# mainboard.net
KiCad netlist of a schematic drawn in EAGLE
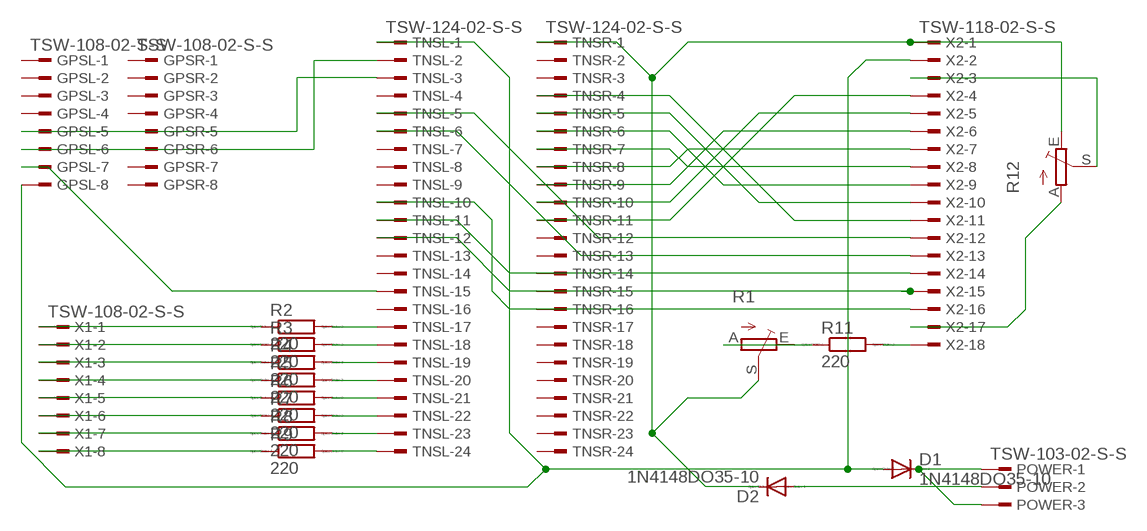
[diagram p0: schematic, sheet 1]

(export (version "E")
  (design (tool "Eeschema 10.0.6"))
  (components
    (comp (ref "D1")
      (value "1N4148DO35-10")
      (footprint "eagle-import:DO35-10")
      (libsource (lib "eagle-import") (part "1N4148DO35-10"))
    )
    (comp (ref "D2")
      (value "1N4148DO35-10")
      (footprint "eagle-import:DO35-10")
      (libsource (lib "eagle-import") (part "1N4148DO35-10"))
    )
    (comp (ref "GPSL")
      (value "TSW-108-02-S-S")
      (footprint "eagle-import:TSW-108-02-S-S")
      (libsource (lib "eagle-import") (part "TSW-108-02-S-S"))
    )
    (comp (ref "GPSR")
      (value "TSW-108-02-S-S")
      (footprint "eagle-import:TSW-108-02-S-S")
      (libsource (lib "eagle-import") (part "TSW-108-02-S-S"))
    )
    (comp (ref "POWER")
      (value "TSW-103-02-S-S")
      (footprint "eagle-import:TSW-103-02-S-S")
      (libsource (lib "eagle-import") (part "TSW-103-02-S-S"))
    )
    (comp (ref "R1")
      (value "TRIM_EU-CA6V")
      (footprint "eagle-import:CA6V")
      (libsource (lib "eagle-import") (part "TRIM_EU-CA6V"))
    )
    (comp (ref "R2")
      (value "220")
      (footprint "eagle-import:0207_10")
      (libsource (lib "eagle-import") (part "R0207/10"))
    )
    (comp (ref "R3")
      (value "220")
      (footprint "eagle-import:0207_10")
      (libsource (lib "eagle-import") (part "R0207/10"))
    )
    (comp (ref "R4")
      (value "220")
      (footprint "eagle-import:0207_10")
      (libsource (lib "eagle-import") (part "R0207/10"))
    )
    (comp (ref "R5")
      (value "220")
      (footprint "eagle-import:0207_10")
      (libsource (lib "eagle-import") (part "R0207/10"))
    )
    (comp (ref "R6")
      (value "220")
      (footprint "eagle-import:0207_10")
      (libsource (lib "eagle-import") (part "R0207/10"))
    )
    (comp (ref "R7")
      (value "220")
      (footprint "eagle-import:0207_10")
      (libsource (lib "eagle-import") (part "R0207/10"))
    )
    (comp (ref "R8")
      (value "220")
      (footprint "eagle-import:0207_10")
      (libsource (lib "eagle-import") (part "R0207/10"))
    )
    (comp (ref "R9")
      (value "220")
      (footprint "eagle-import:0207_10")
      (libsource (lib "eagle-import") (part "R0207/10"))
    )
    (comp (ref "R11")
      (value "220")
      (footprint "eagle-import:0207_10")
      (libsource (lib "eagle-import") (part "R0207/10"))
    )
    (comp (ref "R12")
      (value "TRIM_EU-CA6V")
      (footprint "eagle-import:CA6V")
      (libsource (lib "eagle-import") (part "TRIM_EU-CA6V"))
    )
    (comp (ref "TNSL")
      (value "TSW-124-02-S-S")
      (footprint "eagle-import:TSW-124-02-S-S")
      (libsource (lib "eagle-import") (part "TSW-124-02-S-S"))
    )
    (comp (ref "TNSR")
      (value "TSW-124-02-S-S")
      (footprint "eagle-import:TSW-124-02-S-S")
      (libsource (lib "eagle-import") (part "TSW-124-02-S-S"))
    )
    (comp (ref "X1")
      (value "TSW-108-02-S-S")
      (footprint "eagle-import:TSW-108-02-S-S")
      (libsource (lib "eagle-import") (part "TSW-108-02-S-S"))
    )
    (comp (ref "X2")
      (value "TSW-118-02-S-S")
      (footprint "eagle-import:TSW-118-02-S-S")
      (libsource (lib "eagle-import") (part "TSW-118-02-S-S"))
    )
  )
  (nets
    (net (code "1") (name "Net-(D2-PadC)") (class "Default")
      (node (ref "D2") (pin "C") (pinfunction "C_C") (pintype "passive"))
      (node (ref "R1") (pin "S") (pinfunction "S_S") (pintype "passive"))
      (node (ref "R12") (pin "E") (pinfunction "E_E") (pintype "passive"))
      (node (ref "TNSR") (pin "1") (pinfunction "1_1") (pintype "passive"))
      (node (ref "X2") (pin "1") (pinfunction "1_1") (pintype "passive"))
    )
    (net (code "2") (name "Net-(GPSLE-1)") (class "Default")
      (node (ref "GPSL") (pin "5") (pinfunction "1_5") (pintype "passive"))
      (node (ref "TNSL") (pin "3") (pinfunction "1_3") (pintype "passive"))
    )
    (net (code "3") (name "Net-(GPSLF-1)") (class "Default")
      (node (ref "GPSL") (pin "6") (pinfunction "1_6") (pintype "passive"))
      (node (ref "TNSL") (pin "2") (pinfunction "1_2") (pintype "passive"))
    )
    (net (code "4") (name "Net-(GPSLG-1)") (class "Default")
      (node (ref "GPSL") (pin "7") (pinfunction "1_7") (pintype "passive"))
      (node (ref "TNSL") (pin "15") (pinfunction "1_15") (pintype "passive"))
    )
    (net (code "5") (name "Net-(GPSLH-1)") (class "Default")
      (node (ref "D1") (pin "A") (pinfunction "A_A") (pintype "passive"))
      (node (ref "GPSL") (pin "8") (pinfunction "1_8") (pintype "passive"))
      (node (ref "TNSL") (pin "1") (pinfunction "1_1") (pintype "passive"))
      (node (ref "X2") (pin "2") (pinfunction "1_2") (pintype "passive"))
    )
    (net (code "6") (name "Net-(POWERB-1)") (class "Default")
      (node (ref "D2") (pin "A") (pinfunction "A_A") (pintype "passive"))
      (node (ref "POWER") (pin "2") (pinfunction "1_2") (pintype "passive"))
    )
    (net (code "7") (name "Net-(POWERC-1)") (class "Default")
      (node (ref "D1") (pin "C") (pinfunction "C_C") (pintype "passive"))
      (node (ref "POWER") (pin "1") (pinfunction "1_1") (pintype "passive"))
      (node (ref "POWER") (pin "3") (pinfunction "1_3") (pintype "passive"))
    )
    (net (code "8") (name "Net-(R1-PadA)") (class "Default")
      (node (ref "R1") (pin "A") (pinfunction "A_A") (pintype "passive"))
      (node (ref "R11") (pin "1") (pinfunction "1_1") (pintype "passive"))
    )
    (net (code "9") (name "Net-(R2-Pad1)") (class "Default")
      (node (ref "R2") (pin "1") (pinfunction "1_1") (pintype "passive"))
      (node (ref "X1") (pin "1") (pinfunction "1_1") (pintype "passive"))
    )
    (net (code "10") (name "Net-(TNSLB-1)") (class "Default")
      (node (ref "TNSL") (pin "10") (pinfunction "1_10") (pintype "passive"))
      (node (ref "X2") (pin "16") (pinfunction "1_16") (pintype "passive"))
    )
    (net (code "11") (name "Net-(TNSLC-1)") (class "Default")
      (node (ref "TNSL") (pin "11") (pinfunction "1_11") (pintype "passive"))
      (node (ref "X2") (pin "14") (pinfunction "1_14") (pintype "passive"))
    )
    (net (code "12") (name "Net-(TNSLD-1)") (class "Default")
      (node (ref "TNSL") (pin "12") (pinfunction "1_12") (pintype "passive"))
      (node (ref "X2") (pin "15") (pinfunction "1_15") (pintype "passive"))
    )
    (net (code "13") (name "Net-(TNSLI-1)") (class "Default")
      (node (ref "R2") (pin "2") (pinfunction "2_2") (pintype "passive"))
      (node (ref "TNSL") (pin "17") (pinfunction "1_17") (pintype "passive"))
    )
    (net (code "14") (name "Net-(TNSLJ-1)") (class "Default")
      (node (ref "R3") (pin "2") (pinfunction "2_2") (pintype "passive"))
      (node (ref "TNSL") (pin "18") (pinfunction "1_18") (pintype "passive"))
    )
    (net (code "15") (name "Net-(TNSLK-1)") (class "Default")
      (node (ref "R4") (pin "2") (pinfunction "2_2") (pintype "passive"))
      (node (ref "TNSL") (pin "19") (pinfunction "1_19") (pintype "passive"))
    )
    (net (code "16") (name "Net-(TNSLM-1)") (class "Default")
      (node (ref "R5") (pin "2") (pinfunction "2_2") (pintype "passive"))
      (node (ref "TNSL") (pin "20") (pinfunction "1_20") (pintype "passive"))
    )
    (net (code "17") (name "Net-(TNSLN-1)") (class "Default")
      (node (ref "R6") (pin "2") (pinfunction "2_2") (pintype "passive"))
      (node (ref "TNSL") (pin "21") (pinfunction "1_21") (pintype "passive"))
    )
    (net (code "18") (name "Net-(TNSLO-1)") (class "Default")
      (node (ref "R7") (pin "2") (pinfunction "2_2") (pintype "passive"))
      (node (ref "TNSL") (pin "22") (pinfunction "1_22") (pintype "passive"))
    )
    (net (code "19") (name "Net-(TNSLP-1)") (class "Default")
      (node (ref "R8") (pin "2") (pinfunction "2_2") (pintype "passive"))
      (node (ref "TNSL") (pin "23") (pinfunction "1_23") (pintype "passive"))
    )
    (net (code "20") (name "Net-(TNSLQ-1)") (class "Default")
      (node (ref "R9") (pin "2") (pinfunction "2_2") (pintype "passive"))
      (node (ref "TNSL") (pin "24") (pinfunction "1_24") (pintype "passive"))
    )
    (net (code "21") (name "Net-(TNSLT-1)") (class "Default")
      (node (ref "TNSL") (pin "5") (pinfunction "1_5") (pintype "passive"))
      (node (ref "X2") (pin "12") (pinfunction "1_12") (pintype "passive"))
    )
    (net (code "22") (name "Net-(TNSLU-1)") (class "Default")
      (node (ref "TNSL") (pin "6") (pinfunction "1_6") (pintype "passive"))
      (node (ref "X2") (pin "13") (pinfunction "1_13") (pintype "passive"))
    )
    (net (code "23") (name "Net-(TNSRB-1)") (class "Default")
      (node (ref "TNSR") (pin "10") (pinfunction "1_10") (pintype "passive"))
      (node (ref "X2") (pin "5") (pinfunction "1_5") (pintype "passive"))
    )
    (net (code "24") (name "Net-(TNSRC-1)") (class "Default")
      (node (ref "TNSR") (pin "11") (pinfunction "1_11") (pintype "passive"))
      (node (ref "X2") (pin "4") (pinfunction "1_4") (pintype "passive"))
    )
    (net (code "25") (name "Net-(TNSRS-1)") (class "Default")
      (node (ref "TNSR") (pin "4") (pinfunction "1_4") (pintype "passive"))
      (node (ref "X2") (pin "11") (pinfunction "1_11") (pintype "passive"))
    )
    (net (code "26") (name "Net-(TNSRT-1)") (class "Default")
      (node (ref "TNSR") (pin "5") (pinfunction "1_5") (pintype "passive"))
      (node (ref "X2") (pin "10") (pinfunction "1_10") (pintype "passive"))
    )
    (net (code "27") (name "Net-(TNSRU-1)") (class "Default")
      (node (ref "TNSR") (pin "6") (pinfunction "1_6") (pintype "passive"))
      (node (ref "X2") (pin "9") (pinfunction "1_9") (pintype "passive"))
    )
    (net (code "28") (name "Net-(TNSRV-1)") (class "Default")
      (node (ref "TNSR") (pin "7") (pinfunction "1_7") (pintype "passive"))
      (node (ref "X2") (pin "8") (pinfunction "1_8") (pintype "passive"))
    )
    (net (code "29") (name "Net-(TNSRW-1)") (class "Default")
      (node (ref "TNSR") (pin "8") (pinfunction "1_8") (pintype "passive"))
      (node (ref "X2") (pin "7") (pinfunction "1_7") (pintype "passive"))
    )
    (net (code "30") (name "Net-(TNSRX-1)") (class "Default")
      (node (ref "TNSR") (pin "9") (pinfunction "1_9") (pintype "passive"))
      (node (ref "X2") (pin "6") (pinfunction "1_6") (pintype "passive"))
    )
    (net (code "31") (name "Net-(X1B-1)") (class "Default")
      (node (ref "R3") (pin "1") (pinfunction "1_1") (pintype "passive"))
      (node (ref "X1") (pin "2") (pinfunction "1_2") (pintype "passive"))
    )
    (net (code "32") (name "Net-(X1C-1)") (class "Default")
      (node (ref "R4") (pin "1") (pinfunction "1_1") (pintype "passive"))
      (node (ref "X1") (pin "3") (pinfunction "1_3") (pintype "passive"))
    )
    (net (code "33") (name "Net-(X1D-1)") (class "Default")
      (node (ref "R5") (pin "1") (pinfunction "1_1") (pintype "passive"))
      (node (ref "X1") (pin "4") (pinfunction "1_4") (pintype "passive"))
    )
    (net (code "34") (name "Net-(X1E-1)") (class "Default")
      (node (ref "R6") (pin "1") (pinfunction "1_1") (pintype "passive"))
      (node (ref "X1") (pin "5") (pinfunction "1_5") (pintype "passive"))
    )
    (net (code "35") (name "Net-(X1F-1)") (class "Default")
      (node (ref "R7") (pin "1") (pinfunction "1_1") (pintype "passive"))
      (node (ref "X1") (pin "6") (pinfunction "1_6") (pintype "passive"))
    )
    (net (code "36") (name "Net-(X1G-1)") (class "Default")
      (node (ref "R8") (pin "1") (pinfunction "1_1") (pintype "passive"))
      (node (ref "X1") (pin "7") (pinfunction "1_7") (pintype "passive"))
    )
    (net (code "37") (name "Net-(X1H-1)") (class "Default")
      (node (ref "R9") (pin "1") (pinfunction "1_1") (pintype "passive"))
      (node (ref "X1") (pin "8") (pinfunction "1_8") (pintype "passive"))
    )
    (net (code "38") (name "Net-(X2I-1)") (class "Default")
      (node (ref "R12") (pin "A") (pinfunction "A_A") (pintype "passive"))
      (node (ref "X2") (pin "17") (pinfunction "1_17") (pintype "passive"))
    )
    (net (code "39") (name "Net-(X2J-1)") (class "Default")
      (node (ref "R11") (pin "2") (pinfunction "2_2") (pintype "passive"))
      (node (ref "X2") (pin "18") (pinfunction "1_18") (pintype "passive"))
    )
    (net (code "40") (name "Net-(X2L-1)") (class "Default")
      (node (ref "R12") (pin "S") (pinfunction "S_S") (pintype "passive"))
      (node (ref "X2") (pin "3") (pinfunction "1_3") (pintype "passive"))
    )
    (net (code "41") (name "unconnected-(GPSL-Pad1)") (class "Default")
      (node (ref "GPSL") (pin "1") (pinfunction "1_1") (pintype "passive"))
    )
    (net (code "42") (name "unconnected-(GPSLB-1-Pad2)") (class "Default")
      (node (ref "GPSL") (pin "2") (pinfunction "1_2") (pintype "passive"))
    )
    (net (code "43") (name "unconnected-(GPSLC-1-Pad3)") (class "Default")
      (node (ref "GPSL") (pin "3") (pinfunction "1_3") (pintype "passive"))
    )
    (net (code "44") (name "unconnected-(GPSLD-1-Pad4)") (class "Default")
      (node (ref "GPSL") (pin "4") (pinfunction "1_4") (pintype "passive"))
    )
    (net (code "45") (name "unconnected-(GPSR-Pad1)") (class "Default")
      (node (ref "GPSR") (pin "1") (pinfunction "1_1") (pintype "passive"))
    )
    (net (code "46") (name "unconnected-(GPSRB-1-Pad2)") (class "Default")
      (node (ref "GPSR") (pin "2") (pinfunction "1_2") (pintype "passive"))
    )
    (net (code "47") (name "unconnected-(GPSRC-1-Pad3)") (class "Default")
      (node (ref "GPSR") (pin "3") (pinfunction "1_3") (pintype "passive"))
    )
    (net (code "48") (name "unconnected-(GPSRD-1-Pad4)") (class "Default")
      (node (ref "GPSR") (pin "4") (pinfunction "1_4") (pintype "passive"))
    )
    (net (code "49") (name "unconnected-(GPSRE-1-Pad5)") (class "Default")
      (node (ref "GPSR") (pin "5") (pinfunction "1_5") (pintype "passive"))
    )
    (net (code "50") (name "unconnected-(GPSRF-1-Pad6)") (class "Default")
      (node (ref "GPSR") (pin "6") (pinfunction "1_6") (pintype "passive"))
    )
    (net (code "51") (name "unconnected-(GPSRG-1-Pad7)") (class "Default")
      (node (ref "GPSR") (pin "7") (pinfunction "1_7") (pintype "passive"))
    )
    (net (code "52") (name "unconnected-(GPSRH-1-Pad8)") (class "Default")
      (node (ref "GPSR") (pin "8") (pinfunction "1_8") (pintype "passive"))
    )
    (net (code "53") (name "unconnected-(R1-PadE)") (class "Default")
      (node (ref "R1") (pin "E") (pinfunction "E_E") (pintype "passive"))
    )
    (net (code "54") (name "unconnected-(TNSLE-1-Pad13)") (class "Default")
      (node (ref "TNSL") (pin "13") (pinfunction "1_13") (pintype "passive"))
    )
    (net (code "55") (name "unconnected-(TNSLF-1-Pad14)") (class "Default")
      (node (ref "TNSL") (pin "14") (pinfunction "1_14") (pintype "passive"))
    )
    (net (code "56") (name "unconnected-(TNSLH-1-Pad16)") (class "Default")
      (node (ref "TNSL") (pin "16") (pinfunction "1_16") (pintype "passive"))
    )
    (net (code "57") (name "unconnected-(TNSLS-1-Pad4)") (class "Default")
      (node (ref "TNSL") (pin "4") (pinfunction "1_4") (pintype "passive"))
    )
    (net (code "58") (name "unconnected-(TNSLV-1-Pad7)") (class "Default")
      (node (ref "TNSL") (pin "7") (pinfunction "1_7") (pintype "passive"))
    )
    (net (code "59") (name "unconnected-(TNSLW-1-Pad8)") (class "Default")
      (node (ref "TNSL") (pin "8") (pinfunction "1_8") (pintype "passive"))
    )
    (net (code "60") (name "unconnected-(TNSLX-1-Pad9)") (class "Default")
      (node (ref "TNSL") (pin "9") (pinfunction "1_9") (pintype "passive"))
    )
    (net (code "61") (name "unconnected-(TNSRD-1-Pad12)") (class "Default")
      (node (ref "TNSR") (pin "12") (pinfunction "1_12") (pintype "passive"))
    )
    (net (code "62") (name "unconnected-(TNSRE-1-Pad13)") (class "Default")
      (node (ref "TNSR") (pin "13") (pinfunction "1_13") (pintype "passive"))
    )
    (net (code "63") (name "unconnected-(TNSRF-1-Pad14)") (class "Default")
      (node (ref "TNSR") (pin "14") (pinfunction "1_14") (pintype "passive"))
    )
    (net (code "64") (name "unconnected-(TNSRG-1-Pad15)") (class "Default")
      (node (ref "TNSR") (pin "15") (pinfunction "1_15") (pintype "passive"))
    )
    (net (code "65") (name "unconnected-(TNSRH-1-Pad16)") (class "Default")
      (node (ref "TNSR") (pin "16") (pinfunction "1_16") (pintype "passive"))
    )
    (net (code "66") (name "unconnected-(TNSRI-1-Pad17)") (class "Default")
      (node (ref "TNSR") (pin "17") (pinfunction "1_17") (pintype "passive"))
    )
    (net (code "67") (name "unconnected-(TNSRJ-1-Pad18)") (class "Default")
      (node (ref "TNSR") (pin "18") (pinfunction "1_18") (pintype "passive"))
    )
    (net (code "68") (name "unconnected-(TNSRK-1-Pad19)") (class "Default")
      (node (ref "TNSR") (pin "19") (pinfunction "1_19") (pintype "passive"))
    )
    (net (code "69") (name "unconnected-(TNSRL-1-Pad2)") (class "Default")
      (node (ref "TNSR") (pin "2") (pinfunction "1_2") (pintype "passive"))
    )
    (net (code "70") (name "unconnected-(TNSRM-1-Pad20)") (class "Default")
      (node (ref "TNSR") (pin "20") (pinfunction "1_20") (pintype "passive"))
    )
    (net (code "71") (name "unconnected-(TNSRN-1-Pad21)") (class "Default")
      (node (ref "TNSR") (pin "21") (pinfunction "1_21") (pintype "passive"))
    )
    (net (code "72") (name "unconnected-(TNSRO-1-Pad22)") (class "Default")
      (node (ref "TNSR") (pin "22") (pinfunction "1_22") (pintype "passive"))
    )
    (net (code "73") (name "unconnected-(TNSRP-1-Pad23)") (class "Default")
      (node (ref "TNSR") (pin "23") (pinfunction "1_23") (pintype "passive"))
    )
    (net (code "74") (name "unconnected-(TNSRQ-1-Pad24)") (class "Default")
      (node (ref "TNSR") (pin "24") (pinfunction "1_24") (pintype "passive"))
    )
    (net (code "75") (name "unconnected-(TNSRR-1-Pad3)") (class "Default")
      (node (ref "TNSR") (pin "3") (pinfunction "1_3") (pintype "passive"))
    )
  )
)
